# Microcontroller.net
KiCad netlist of a schematic drawn in Altium Designer
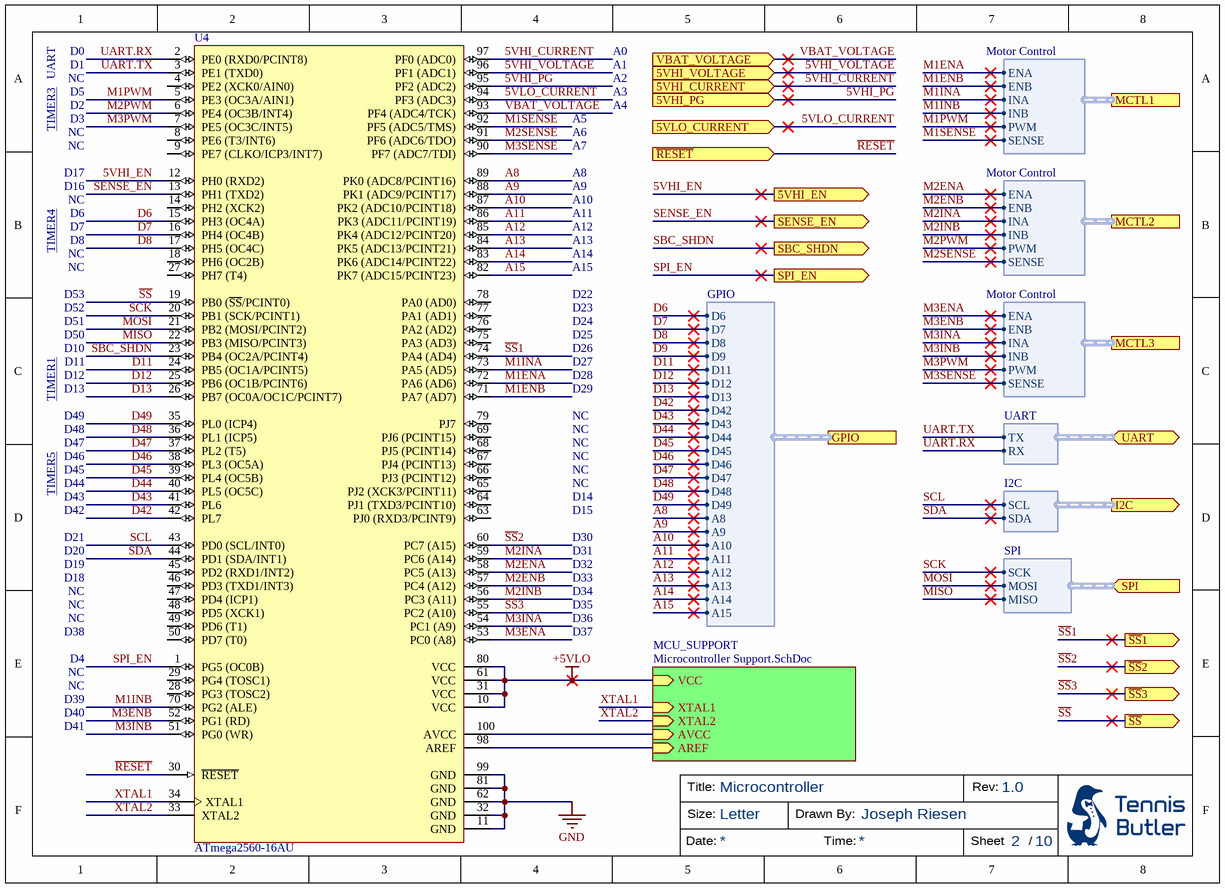
[diagram p0: Microcontroller.SchDoc]

(export (version "E")
  (design (tool "Eeschema 10.0.6"))
  (components
    (comp (ref "U4")
      (value "ATmega2560-16AU")
      (footprint "TSQFP50P1600X1600X120-100M")
      (fields
        (field (name "MANUFACTURER") "Microchip / Atmel")
        (field (name "MANUFACTURER PART NUMBER") "ATMEGA2560-16AU")
      )
      (libsource (lib "ATmega2560-16AU") (part "ATmega2560-16AU"))
    )
  )
  (nets
    (net (code "7") (name "+5VLO") (class "Default")
      (node (ref "U4") (pin "10") (pinfunction "VCC_10") (pintype "power_in"))
      (node (ref "U4") (pin "31") (pinfunction "VCC_31") (pintype "power_in"))
      (node (ref "U4") (pin "61") (pinfunction "VCC_61") (pintype "power_in"))
      (node (ref "U4") (pin "80") (pinfunction "VCC_80") (pintype "power_in"))
    )
    (net (code "8") (name "/5VHI_CURRENT") (class "Default")
      (node (ref "U4") (pin "97") (pinfunction "PF0_(ADC0)_97") (pintype "bidirectional"))
    )
    (net (code "9") (name "/5VHI_EN") (class "Default")
      (node (ref "U4") (pin "12") (pinfunction "PH0_(RXD2)_12") (pintype "bidirectional"))
    )
    (net (code "10") (name "/5VHI_PG") (class "Default")
      (node (ref "U4") (pin "95") (pinfunction "PF2_(ADC2)_95") (pintype "bidirectional"))
    )
    (net (code "11") (name "/5VHI_VOLTAGE") (class "Default")
      (node (ref "U4") (pin "96") (pinfunction "PF1_(ADC1)_96") (pintype "bidirectional"))
    )
    (net (code "12") (name "/5VLO_CURRENT") (class "Default")
      (node (ref "U4") (pin "94") (pinfunction "PF3_(ADC3)_94") (pintype "bidirectional"))
    )
    (net (code "13") (name "/A8") (class "Default")
      (node (ref "U4") (pin "89") (pinfunction "PK0_(ADC8/PCINT16)_89") (pintype "bidirectional"))
    )
    (net (code "14") (name "/A9") (class "Default")
      (node (ref "U4") (pin "88") (pinfunction "PK1_(ADC9/PCINT17)_88") (pintype "bidirectional"))
    )
    (net (code "15") (name "/A10") (class "Default")
      (node (ref "U4") (pin "87") (pinfunction "PK2_(ADC10/PCINT18)_87") (pintype "bidirectional"))
    )
    (net (code "16") (name "/A11") (class "Default")
      (node (ref "U4") (pin "86") (pinfunction "PK3_(ADC11/PCINT19)_86") (pintype "bidirectional"))
    )
    (net (code "17") (name "/A12") (class "Default")
      (node (ref "U4") (pin "85") (pinfunction "PK4_(ADC12/PCINT20)_85") (pintype "bidirectional"))
    )
    (net (code "18") (name "/A13") (class "Default")
      (node (ref "U4") (pin "84") (pinfunction "PK5_(ADC13/PCINT21)_84") (pintype "bidirectional"))
    )
    (net (code "19") (name "/A14") (class "Default")
      (node (ref "U4") (pin "83") (pinfunction "PK6_(ADC14/PCINT22)_83") (pintype "bidirectional"))
    )
    (net (code "20") (name "/A15") (class "Default")
      (node (ref "U4") (pin "82") (pinfunction "PK7_(ADC15/PCINT23)_82") (pintype "bidirectional"))
    )
    (net (code "21") (name "/AREF") (class "Default")
      (node (ref "U4") (pin "98") (pinfunction "AREF_98") (pintype "power_in"))
    )
    (net (code "22") (name "/AVCC") (class "Default")
      (node (ref "U4") (pin "100") (pinfunction "AVCC_100") (pintype "power_in"))
    )
    (net (code "23") (name "/D6") (class "Default")
      (node (ref "U4") (pin "15") (pinfunction "PH3_(OC4A)_15") (pintype "bidirectional"))
    )
    (net (code "24") (name "/D7") (class "Default")
      (node (ref "U4") (pin "16") (pinfunction "PH4_(OC4B)_16") (pintype "bidirectional"))
    )
    (net (code "25") (name "/D8") (class "Default")
      (node (ref "U4") (pin "17") (pinfunction "PH5_(OC4C)_17") (pintype "bidirectional"))
    )
    (net (code "27") (name "/D11") (class "Default")
      (node (ref "U4") (pin "24") (pinfunction "PB5_(OC1A/PCINT5)_24") (pintype "bidirectional"))
    )
    (net (code "28") (name "/D12") (class "Default")
      (node (ref "U4") (pin "25") (pinfunction "PB6_(OC1B/PCINT6)_25") (pintype "bidirectional"))
    )
    (net (code "29") (name "/D13") (class "Default")
      (node (ref "U4") (pin "26") (pinfunction "PB7_(OC0A/OC1C/PCINT7)_26") (pintype "bidirectional"))
    )
    (net (code "30") (name "/D42") (class "Default")
      (node (ref "U4") (pin "42") (pinfunction "PL7_42") (pintype "bidirectional"))
    )
    (net (code "31") (name "/D43") (class "Default")
      (node (ref "U4") (pin "41") (pinfunction "PL6_41") (pintype "bidirectional"))
    )
    (net (code "32") (name "/D44") (class "Default")
      (node (ref "U4") (pin "40") (pinfunction "PL5_(OC5C)_40") (pintype "bidirectional"))
    )
    (net (code "33") (name "/D45") (class "Default")
      (node (ref "U4") (pin "39") (pinfunction "PL4_(OC5B)_39") (pintype "bidirectional"))
    )
    (net (code "34") (name "/D46") (class "Default")
      (node (ref "U4") (pin "38") (pinfunction "PL3_(OC5A)_38") (pintype "bidirectional"))
    )
    (net (code "35") (name "/D47") (class "Default")
      (node (ref "U4") (pin "37") (pinfunction "PL2_(T5)_37") (pintype "bidirectional"))
    )
    (net (code "36") (name "/D48") (class "Default")
      (node (ref "U4") (pin "36") (pinfunction "PL1_(ICP5)_36") (pintype "bidirectional"))
    )
    (net (code "37") (name "/D49") (class "Default")
      (node (ref "U4") (pin "35") (pinfunction "PL0_(ICP4)_35") (pintype "bidirectional"))
    )
    (net (code "38") (name "/M1ENA") (class "Default")
      (node (ref "U4") (pin "72") (pinfunction "PA6_(AD6)_72") (pintype "bidirectional"))
    )
    (net (code "39") (name "/M1ENB") (class "Default")
      (node (ref "U4") (pin "71") (pinfunction "PA7_(AD7)_71") (pintype "bidirectional"))
    )
    (net (code "40") (name "/M1INA") (class "Default")
      (node (ref "U4") (pin "73") (pinfunction "PA5_(AD5)_73") (pintype "bidirectional"))
    )
    (net (code "41") (name "/M1INB") (class "Default")
      (node (ref "U4") (pin "70") (pinfunction "PG2_(ALE)_70") (pintype "bidirectional"))
    )
    (net (code "42") (name "/M1PWM") (class "Default")
      (node (ref "U4") (pin "5") (pinfunction "PE3_(OC3A/AIN1)_5") (pintype "bidirectional"))
    )
    (net (code "43") (name "/M1SENSE") (class "Default")
      (node (ref "U4") (pin "92") (pinfunction "PF5_(ADC5/TMS)_92") (pintype "bidirectional"))
    )
    (net (code "44") (name "/M2ENA") (class "Default")
      (node (ref "U4") (pin "58") (pinfunction "PC5_(A13)_58") (pintype "bidirectional"))
    )
    (net (code "45") (name "/M2ENB") (class "Default")
      (node (ref "U4") (pin "57") (pinfunction "PC4_(A12)_57") (pintype "bidirectional"))
    )
    (net (code "46") (name "/M2INA") (class "Default")
      (node (ref "U4") (pin "59") (pinfunction "PC6_(A14)_59") (pintype "bidirectional"))
    )
    (net (code "47") (name "/M2INB") (class "Default")
      (node (ref "U4") (pin "56") (pinfunction "PC3_(A11)_56") (pintype "bidirectional"))
    )
    (net (code "48") (name "/M2PWM") (class "Default")
      (node (ref "U4") (pin "6") (pinfunction "PE4_(OC3B/INT4)_6") (pintype "bidirectional"))
    )
    (net (code "49") (name "/M2SENSE") (class "Default")
      (node (ref "U4") (pin "91") (pinfunction "PF6_(ADC6/TDO)_91") (pintype "bidirectional"))
    )
    (net (code "50") (name "/M3ENA") (class "Default")
      (node (ref "U4") (pin "53") (pinfunction "PC0_(A8)_53") (pintype "bidirectional"))
    )
    (net (code "51") (name "/M3ENB") (class "Default")
      (node (ref "U4") (pin "52") (pinfunction "PG1_(RD)_52") (pintype "bidirectional"))
    )
    (net (code "52") (name "/M3INA") (class "Default")
      (node (ref "U4") (pin "54") (pinfunction "PC1_(A9)_54") (pintype "bidirectional"))
    )
    (net (code "53") (name "/M3INB") (class "Default")
      (node (ref "U4") (pin "51") (pinfunction "PG0_(WR)_51") (pintype "bidirectional"))
    )
    (net (code "54") (name "/M3PWM") (class "Default")
      (node (ref "U4") (pin "7") (pinfunction "PE5_(OC3C/INT5)_7") (pintype "bidirectional"))
    )
    (net (code "55") (name "/M3SENSE") (class "Default")
      (node (ref "U4") (pin "90") (pinfunction "PF7_(ADC7/TDI)_90") (pintype "bidirectional"))
    )
    (net (code "56") (name "/MISO") (class "Default")
      (node (ref "U4") (pin "22") (pinfunction "PB3_(MISO/PCINT3)_22") (pintype "bidirectional"))
    )
    (net (code "57") (name "/MOSI") (class "Default")
      (node (ref "U4") (pin "21") (pinfunction "PB2_(MOSI/PCINT2)_21") (pintype "bidirectional"))
    )
    (net (code "58") (name "/SBC_SHDN") (class "Default")
      (node (ref "U4") (pin "23") (pinfunction "PB4_(OC2A/PCINT4)_23") (pintype "bidirectional"))
    )
    (net (code "59") (name "/SCK") (class "Default")
      (node (ref "U4") (pin "20") (pinfunction "PB1_(SCK/PCINT1)_20") (pintype "bidirectional"))
    )
    (net (code "60") (name "/SCL") (class "Default")
      (node (ref "U4") (pin "43") (pinfunction "PD0_(SCL/INT0)_43") (pintype "bidirectional"))
    )
    (net (code "61") (name "/SDA") (class "Default")
      (node (ref "U4") (pin "44") (pinfunction "PD1_(SDA/INT1)_44") (pintype "bidirectional"))
    )
    (net (code "62") (name "/SENSE_EN") (class "Default")
      (node (ref "U4") (pin "13") (pinfunction "PH1_(TXD2)_13") (pintype "bidirectional"))
    )
    (net (code "63") (name "/SPI_EN") (class "Default")
      (node (ref "U4") (pin "1") (pinfunction "PG5_(OC0B)_1") (pintype "bidirectional"))
    )
    (net (code "64") (name "/UART.RX") (class "Default")
      (node (ref "U4") (pin "2") (pinfunction "PE0_(RXD0/PCINT8)_2") (pintype "bidirectional"))
    )
    (net (code "65") (name "/UART.TX") (class "Default")
      (node (ref "U4") (pin "3") (pinfunction "PE1_(TXD0)_3") (pintype "bidirectional"))
    )
    (net (code "66") (name "/VBAT_VOLTAGE") (class "Default")
      (node (ref "U4") (pin "93") (pinfunction "PF4_(ADC4/TCK)_93") (pintype "bidirectional"))
    )
    (net (code "67") (name "/XTAL1") (class "Default")
      (node (ref "U4") (pin "34") (pinfunction "XTAL1_34") (pintype "passive"))
    )
    (net (code "68") (name "/XTAL2") (class "Default")
      (node (ref "U4") (pin "33") (pinfunction "XTAL2_33") (pintype "passive"))
    )
    (net (code "74") (name "/~{RESET}") (class "Default")
      (node (ref "U4") (pin "30") (pinfunction "~{RESET}_30") (pintype "input"))
    )
    (net (code "75") (name "/~{SS}") (class "Default")
      (node (ref "U4") (pin "19") (pinfunction "PB0_(~{SS}/PCINT0)_19") (pintype "bidirectional"))
    )
    (net (code "76") (name "/~{SS}1") (class "Default")
      (node (ref "U4") (pin "74") (pinfunction "PA4_(AD4)_74") (pintype "bidirectional"))
    )
    (net (code "77") (name "/~{SS}2") (class "Default")
      (node (ref "U4") (pin "60") (pinfunction "PC7_(A15)_60") (pintype "bidirectional"))
    )
    (net (code "78") (name "/~{SS}3") (class "Default")
      (node (ref "U4") (pin "55") (pinfunction "PC2_(A10)_55") (pintype "bidirectional"))
    )
    (net (code "79") (name "GND") (class "Default")
      (node (ref "U4") (pin "11") (pinfunction "GND_11") (pintype "power_in"))
      (node (ref "U4") (pin "32") (pinfunction "GND_32") (pintype "power_in"))
      (node (ref "U4") (pin "62") (pinfunction "GND_62") (pintype "power_in"))
      (node (ref "U4") (pin "81") (pinfunction "GND_81") (pintype "power_in"))
      (node (ref "U4") (pin "99") (pinfunction "GND_99") (pintype "power_in"))
    )
    (net (code "80") (name "unconnected-(U4-PA0_(AD0)-Pad78)") (class "Default")
      (node (ref "U4") (pin "78") (pinfunction "PA0_(AD0)_78") (pintype "bidirectional"))
    )
    (net (code "81") (name "unconnected-(U4-PA1_(AD1)-Pad77)") (class "Default")
      (node (ref "U4") (pin "77") (pinfunction "PA1_(AD1)_77") (pintype "bidirectional"))
    )
    (net (code "82") (name "unconnected-(U4-PA2_(AD2)-Pad76)") (class "Default")
      (node (ref "U4") (pin "76") (pinfunction "PA2_(AD2)_76") (pintype "bidirectional"))
    )
    (net (code "83") (name "unconnected-(U4-PA3_(AD3)-Pad75)") (class "Default")
      (node (ref "U4") (pin "75") (pinfunction "PA3_(AD3)_75") (pintype "bidirectional"))
    )
    (net (code "84") (name "unconnected-(U4-PD2_(RXD1{slash}INT2)-Pad45)") (class "Default")
      (node (ref "U4") (pin "45") (pinfunction "PD2_(RXD1/INT2)_45") (pintype "bidirectional"))
    )
    (net (code "85") (name "unconnected-(U4-PD3_(TXD1{slash}INT3)-Pad46)") (class "Default")
      (node (ref "U4") (pin "46") (pinfunction "PD3_(TXD1/INT3)_46") (pintype "bidirectional"))
    )
    (net (code "86") (name "unconnected-(U4-PD4_(ICP1)-Pad47)") (class "Default")
      (node (ref "U4") (pin "47") (pinfunction "PD4_(ICP1)_47") (pintype "bidirectional"))
    )
    (net (code "87") (name "unconnected-(U4-PD5_(XCK1)-Pad48)") (class "Default")
      (node (ref "U4") (pin "48") (pinfunction "PD5_(XCK1)_48") (pintype "bidirectional"))
    )
    (net (code "88") (name "unconnected-(U4-PD6_(T1)-Pad49)") (class "Default")
      (node (ref "U4") (pin "49") (pinfunction "PD6_(T1)_49") (pintype "bidirectional"))
    )
    (net (code "89") (name "unconnected-(U4-PD7_(T0)-Pad50)") (class "Default")
      (node (ref "U4") (pin "50") (pinfunction "PD7_(T0)_50") (pintype "bidirectional"))
    )
    (net (code "90") (name "unconnected-(U4-PE2_(XCK0{slash}AIN0)-Pad4)") (class "Default")
      (node (ref "U4") (pin "4") (pinfunction "PE2_(XCK0/AIN0)_4") (pintype "bidirectional"))
    )
    (net (code "91") (name "unconnected-(U4-PE6_(T3{slash}INT6)-Pad8)") (class "Default")
      (node (ref "U4") (pin "8") (pinfunction "PE6_(T3/INT6)_8") (pintype "bidirectional"))
    )
    (net (code "92") (name "unconnected-(U4-PE7_(CLKO{slash}ICP3{slash}INT7)-Pad9)") (class "Default")
      (node (ref "U4") (pin "9") (pinfunction "PE7_(CLKO/ICP3/INT7)_9") (pintype "bidirectional"))
    )
    (net (code "93") (name "unconnected-(U4-PG3_(TOSC2)-Pad28)") (class "Default")
      (node (ref "U4") (pin "28") (pinfunction "PG3_(TOSC2)_28") (pintype "bidirectional"))
    )
    (net (code "94") (name "unconnected-(U4-PG4_(TOSC1)-Pad29)") (class "Default")
      (node (ref "U4") (pin "29") (pinfunction "PG4_(TOSC1)_29") (pintype "bidirectional"))
    )
    (net (code "95") (name "unconnected-(U4-PH2_(XCK2)-Pad14)") (class "Default")
      (node (ref "U4") (pin "14") (pinfunction "PH2_(XCK2)_14") (pintype "bidirectional"))
    )
    (net (code "96") (name "unconnected-(U4-PH6_(OC2B)-Pad18)") (class "Default")
      (node (ref "U4") (pin "18") (pinfunction "PH6_(OC2B)_18") (pintype "bidirectional"))
    )
    (net (code "97") (name "unconnected-(U4-PH7_(T4)-Pad27)") (class "Default")
      (node (ref "U4") (pin "27") (pinfunction "PH7_(T4)_27") (pintype "bidirectional"))
    )
    (net (code "98") (name "unconnected-(U4-PJ0_(RXD3{slash}PCINT9)-Pad63)") (class "Default")
      (node (ref "U4") (pin "63") (pinfunction "PJ0_(RXD3/PCINT9)_63") (pintype "bidirectional"))
    )
    (net (code "99") (name "unconnected-(U4-PJ1_(TXD3{slash}PCINT10)-Pad64)") (class "Default")
      (node (ref "U4") (pin "64") (pinfunction "PJ1_(TXD3/PCINT10)_64") (pintype "bidirectional"))
    )
    (net (code "100") (name "unconnected-(U4-PJ2_(XCK3{slash}PCINT11)-Pad65)") (class "Default")
      (node (ref "U4") (pin "65") (pinfunction "PJ2_(XCK3/PCINT11)_65") (pintype "bidirectional"))
    )
    (net (code "101") (name "unconnected-(U4-PJ3_(PCINT12)-Pad66)") (class "Default")
      (node (ref "U4") (pin "66") (pinfunction "PJ3_(PCINT12)_66") (pintype "bidirectional"))
    )
    (net (code "102") (name "unconnected-(U4-PJ4_(PCINT13)-Pad67)") (class "Default")
      (node (ref "U4") (pin "67") (pinfunction "PJ4_(PCINT13)_67") (pintype "bidirectional"))
    )
    (net (code "103") (name "unconnected-(U4-PJ5_(PCINT14)-Pad68)") (class "Default")
      (node (ref "U4") (pin "68") (pinfunction "PJ5_(PCINT14)_68") (pintype "bidirectional"))
    )
    (net (code "104") (name "unconnected-(U4-PJ6_(PCINT15)-Pad69)") (class "Default")
      (node (ref "U4") (pin "69") (pinfunction "PJ6_(PCINT15)_69") (pintype "bidirectional"))
    )
    (net (code "105") (name "unconnected-(U4-PJ7-Pad79)") (class "Default")
      (node (ref "U4") (pin "79") (pinfunction "PJ7_79") (pintype "bidirectional"))
    )
  )
)
